# ma732_adapter.net
KiCad netlist of a schematic drawn in EAGLE
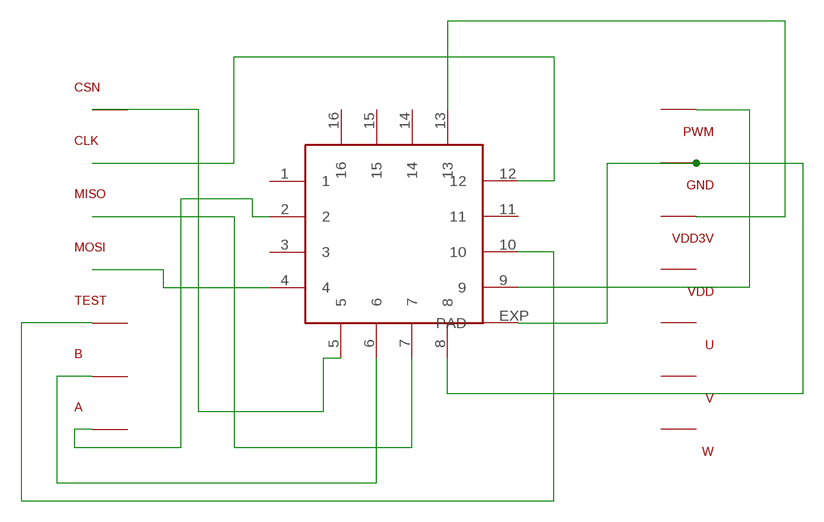
[diagram p0: schematic, sheet 1]

(export (version "E")
  (design (tool "Eeschema 10.0.6"))
  (components
    (comp (ref "A")
      (value "TSSOP_PAD")
      (footprint "eagle-import:TSSOP_PAD")
      (libsource (lib "eagle-import") (part "TSSOP_PAD"))
    )
    (comp (ref "B")
      (value "TSSOP_PAD")
      (footprint "eagle-import:TSSOP_PAD")
      (libsource (lib "eagle-import") (part "TSSOP_PAD"))
    )
    (comp (ref "CLK")
      (value "TSSOP_PAD")
      (footprint "eagle-import:TSSOP_PAD")
      (libsource (lib "eagle-import") (part "TSSOP_PAD"))
    )
    (comp (ref "CSN")
      (value "TSSOP_PAD")
      (footprint "eagle-import:TSSOP_PAD")
      (libsource (lib "eagle-import") (part "TSSOP_PAD"))
    )
    (comp (ref "GND")
      (value "TSSOP_PAD")
      (footprint "eagle-import:TSSOP_PAD")
      (libsource (lib "eagle-import") (part "TSSOP_PAD"))
    )
    (comp (ref "MISO")
      (value "TSSOP_PAD")
      (footprint "eagle-import:TSSOP_PAD")
      (libsource (lib "eagle-import") (part "TSSOP_PAD"))
    )
    (comp (ref "MOSI")
      (value "TSSOP_PAD")
      (footprint "eagle-import:TSSOP_PAD")
      (libsource (lib "eagle-import") (part "TSSOP_PAD"))
    )
    (comp (ref "PWM")
      (value "TSSOP_PAD")
      (footprint "eagle-import:TSSOP_PAD")
      (libsource (lib "eagle-import") (part "TSSOP_PAD"))
    )
    (comp (ref "TEST")
      (value "TSSOP_PAD")
      (footprint "eagle-import:TSSOP_PAD")
      (libsource (lib "eagle-import") (part "TSSOP_PAD"))
    )
    (comp (ref "U")
      (value "TSSOP_PAD")
      (footprint "eagle-import:TSSOP_PAD")
      (libsource (lib "eagle-import") (part "TSSOP_PAD"))
    )
    (comp (ref "U$1")
      (value "QFN16-BO")
      (footprint "eagle-import:QFN16")
      (libsource (lib "eagle-import") (part "QFN16-BO"))
    )
    (comp (ref "V")
      (value "TSSOP_PAD")
      (footprint "eagle-import:TSSOP_PAD")
      (libsource (lib "eagle-import") (part "TSSOP_PAD"))
    )
    (comp (ref "VDD")
      (value "TSSOP_PAD")
      (footprint "eagle-import:TSSOP_PAD")
      (libsource (lib "eagle-import") (part "TSSOP_PAD"))
    )
    (comp (ref "VDD3V")
      (value "TSSOP_PAD")
      (footprint "eagle-import:TSSOP_PAD")
      (libsource (lib "eagle-import") (part "TSSOP_PAD"))
    )
    (comp (ref "W")
      (value "TSSOP_PAD")
      (footprint "eagle-import:TSSOP_PAD")
      (libsource (lib "eagle-import") (part "TSSOP_PAD"))
    )
  )
  (nets
    (net (code "1") (name "Net-(A-PadP$1)") (class "Default")
      (node (ref "A") (pin "P$1") (pinfunction "P$1_P$1") (pintype "bidirectional"))
      (node (ref "U$1") (pin "2") (pinfunction "2_2") (pintype "bidirectional"))
    )
    (net (code "2") (name "Net-(B-PadP$1)") (class "Default")
      (node (ref "B") (pin "P$1") (pinfunction "P$1_P$1") (pintype "bidirectional"))
      (node (ref "U$1") (pin "6") (pinfunction "6_6") (pintype "bidirectional"))
    )
    (net (code "3") (name "Net-(CLK-PadP$1)") (class "Default")
      (node (ref "CLK") (pin "P$1") (pinfunction "P$1_P$1") (pintype "bidirectional"))
      (node (ref "U$1") (pin "12") (pinfunction "12_12") (pintype "bidirectional"))
    )
    (net (code "4") (name "Net-(CSN-PadP$1)") (class "Default")
      (node (ref "CSN") (pin "P$1") (pinfunction "P$1_P$1") (pintype "bidirectional"))
      (node (ref "U$1") (pin "5") (pinfunction "5_5") (pintype "bidirectional"))
    )
    (net (code "5") (name "Net-(MISO-PadP$1)") (class "Default")
      (node (ref "MISO") (pin "P$1") (pinfunction "P$1_P$1") (pintype "bidirectional"))
      (node (ref "U$1") (pin "7") (pinfunction "7_7") (pintype "bidirectional"))
    )
    (net (code "6") (name "Net-(MOSI-PadP$1)") (class "Default")
      (node (ref "MOSI") (pin "P$1") (pinfunction "P$1_P$1") (pintype "bidirectional"))
      (node (ref "U$1") (pin "4") (pinfunction "4_4") (pintype "bidirectional"))
    )
    (net (code "7") (name "Net-(PWM-PadP$1)") (class "Default")
      (node (ref "PWM") (pin "P$1") (pinfunction "P$1_P$1") (pintype "bidirectional"))
      (node (ref "U$1") (pin "9") (pinfunction "9_9") (pintype "bidirectional"))
    )
    (net (code "8") (name "Net-(TEST-PadP$1)") (class "Default")
      (node (ref "TEST") (pin "P$1") (pinfunction "P$1_P$1") (pintype "bidirectional"))
      (node (ref "U$1") (pin "10") (pinfunction "10_10") (pintype "bidirectional"))
    )
    (net (code "9") (name "Net-(U$1-PAD)") (class "Default")
      (node (ref "GND") (pin "P$1") (pinfunction "P$1_P$1") (pintype "bidirectional"))
      (node (ref "U$1") (pin "8") (pinfunction "8_8") (pintype "bidirectional"))
      (node (ref "U$1") (pin "EXP") (pinfunction "PAD_EXP") (pintype "bidirectional"))
    )
    (net (code "10") (name "Net-(U$1-Pad13)") (class "Default")
      (node (ref "U$1") (pin "13") (pinfunction "13_13") (pintype "bidirectional"))
      (node (ref "VDD3V") (pin "P$1") (pinfunction "P$1_P$1") (pintype "bidirectional"))
    )
    (net (code "11") (name "unconnected-(U$1-Pad1)") (class "Default")
      (node (ref "U$1") (pin "1") (pinfunction "1_1") (pintype "bidirectional"))
    )
    (net (code "12") (name "unconnected-(U$1-Pad3)") (class "Default")
      (node (ref "U$1") (pin "3") (pinfunction "3_3") (pintype "bidirectional"))
    )
    (net (code "13") (name "unconnected-(U$1-Pad11)") (class "Default")
      (node (ref "U$1") (pin "11") (pinfunction "11_11") (pintype "bidirectional"))
    )
    (net (code "14") (name "unconnected-(U$1-Pad14)") (class "Default")
      (node (ref "U$1") (pin "14") (pinfunction "14_14") (pintype "bidirectional"))
    )
    (net (code "15") (name "unconnected-(U$1-Pad15)") (class "Default")
      (node (ref "U$1") (pin "15") (pinfunction "15_15") (pintype "bidirectional"))
    )
    (net (code "16") (name "unconnected-(U$1-Pad16)") (class "Default")
      (node (ref "U$1") (pin "16") (pinfunction "16_16") (pintype "bidirectional"))
    )
    (net (code "17") (name "unconnected-(U-PadP$1)") (class "Default")
      (node (ref "U") (pin "P$1") (pinfunction "P$1_P$1") (pintype "bidirectional"))
    )
    (net (code "18") (name "unconnected-(V-PadP$1)") (class "Default")
      (node (ref "V") (pin "P$1") (pinfunction "P$1_P$1") (pintype "bidirectional"))
    )
    (net (code "19") (name "unconnected-(VDD-PadP$1)") (class "Default")
      (node (ref "VDD") (pin "P$1") (pinfunction "P$1_P$1") (pintype "bidirectional"))
    )
    (net (code "20") (name "unconnected-(W-PadP$1)") (class "Default")
      (node (ref "W") (pin "P$1") (pinfunction "P$1_P$1") (pintype "bidirectional"))
    )
  )
)
